# Program_Counter_Electronic_Scheme_2021-1.net
KiCad netlist of a schematic drawn in Altium Designer
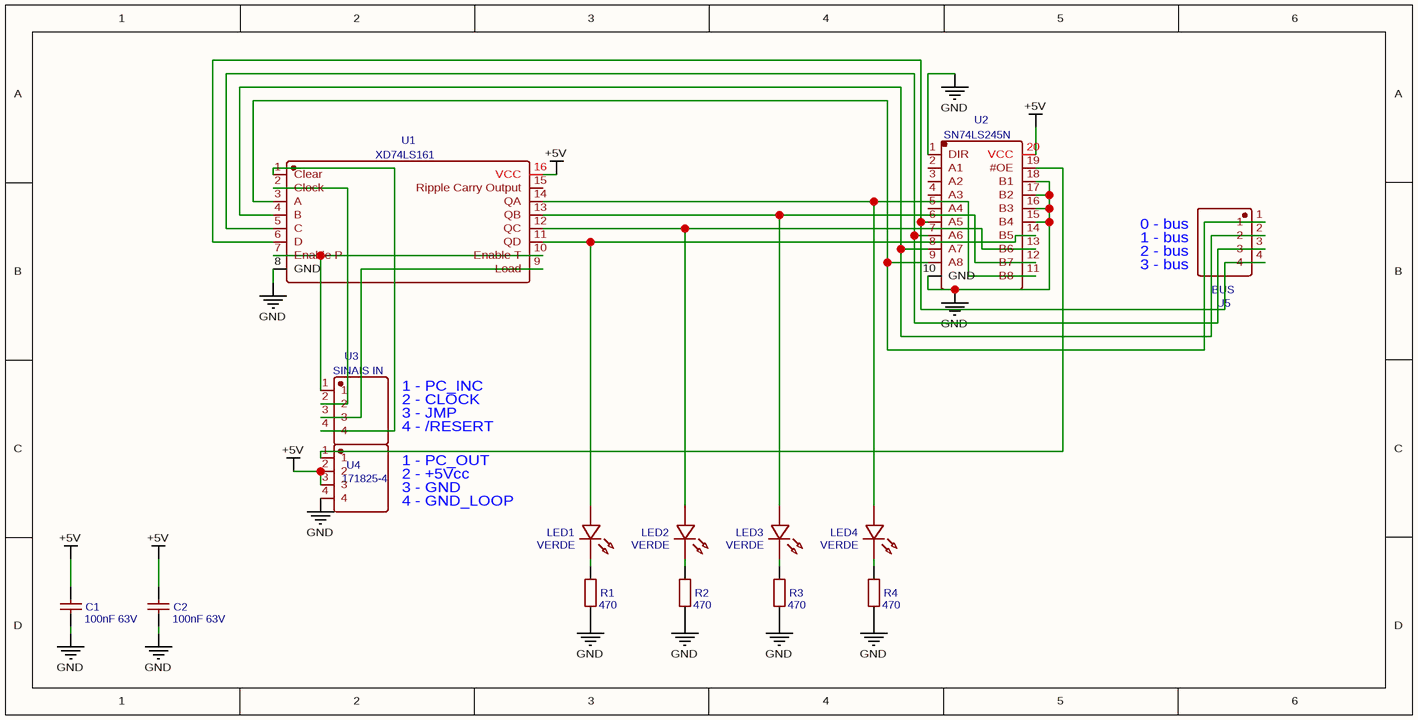
[diagram p0: Program Counter Electronic Scheme_2021-10-28.schdoc]

(export (version "E")
  (design (tool "Eeschema 10.0.6"))
  (components
    (comp (ref "C1")
      (value "100nF 63V")
      (fields
        (field (name "BOM_SUPPLIER PART") "C444741")
        (field (name "BOM_MANUFACTURER PART") "SR305C105KAR")
        (field (name "CONTRIBUTOR") "LCSC")
      )
      (libsource (lib "altium-import") (part "root_3_100nF 63V_"))
    )
    (comp (ref "C2")
      (value "100nF 63V")
      (fields
        (field (name "BOM_SUPPLIER PART") "C444741")
        (field (name "BOM_MANUFACTURER PART") "SR305C105KAR")
        (field (name "CONTRIBUTOR") "LCSC")
      )
      (libsource (lib "altium-import") (part "root_3_100nF 63V_"))
    )
    (comp (ref "LED1")
      (value "VERDE")
      (fields
        (field (name "BOM_SUPPLIER PART") "C605465")
        (field (name "BOM_MANUFACTURER PART") "264-7GD")
        (field (name "CONTRIBUTOR") "LCSC")
      )
      (libsource (lib "altium-import") (part "root_1_VERDE_"))
    )
    (comp (ref "LED2")
      (value "VERDE")
      (fields
        (field (name "BOM_SUPPLIER PART") "C605465")
        (field (name "BOM_MANUFACTURER PART") "264-7GD")
        (field (name "CONTRIBUTOR") "LCSC")
      )
      (libsource (lib "altium-import") (part "root_1_VERDE_"))
    )
    (comp (ref "LED3")
      (value "VERDE")
      (fields
        (field (name "BOM_SUPPLIER PART") "C605465")
        (field (name "BOM_MANUFACTURER PART") "264-7GD")
        (field (name "CONTRIBUTOR") "LCSC")
      )
      (libsource (lib "altium-import") (part "root_1_VERDE_"))
    )
    (comp (ref "LED4")
      (value "VERDE")
      (fields
        (field (name "BOM_SUPPLIER PART") "C605465")
        (field (name "BOM_MANUFACTURER PART") "264-7GD")
        (field (name "CONTRIBUTOR") "LCSC")
      )
      (libsource (lib "altium-import") (part "root_1_VERDE_"))
    )
    (comp (ref "R1")
      (value "470")
      (fields
        (field (name "BOM_MANUFACTURER PART") "CFR02SJ0823A10")
        (field (name "BOM_SUPPLIER PART") "C69876")
      )
      (libsource (lib "altium-import") (part "root_3_470_"))
    )
    (comp (ref "R2")
      (value "470")
      (fields
        (field (name "BOM_MANUFACTURER PART") "CFR02SJ0823A10")
        (field (name "BOM_SUPPLIER PART") "C69876")
      )
      (libsource (lib "altium-import") (part "root_3_470_"))
    )
    (comp (ref "R3")
      (value "470")
      (fields
        (field (name "BOM_MANUFACTURER PART") "CFR02SJ0823A10")
        (field (name "BOM_SUPPLIER PART") "C69876")
      )
      (libsource (lib "altium-import") (part "root_3_470_"))
    )
    (comp (ref "R4")
      (value "470")
      (fields
        (field (name "BOM_MANUFACTURER PART") "CFR02SJ0823A10")
        (field (name "BOM_SUPPLIER PART") "C69876")
      )
      (libsource (lib "altium-import") (part "root_3_470_"))
    )
    (comp (ref "U1")
      (value "XD74LS161")
      (fields (field (name "BOM_SUPPLIER PART") "C609766") (field (name "CONTRIBUTOR") "LCSC"))
      (libsource (lib "altium-import") (part "root_0_XD74LS161_"))
    )
    (comp (ref "U2")
      (value "SN74LS245N")
      (fields (field (name "BOM_SUPPLIER PART") "C352966") (field (name "CONTRIBUTOR") "LCSC"))
      (libsource (lib "altium-import") (part "root_0_SN74LS245N_"))
    )
    (comp (ref "U3")
      (value "SINAIS IN")
      (fields
        (field (name "BOM_SUPPLIER PART") "C210162")
        (field (name "BOM_MANUFACTURER PART") "171825-4")
        (field (name "CONTRIBUTOR") "LCSC")
      )
      (libsource (lib "altium-import") (part "root_0_SINAIS IN_"))
    )
    (comp (ref "U4")
      (value "171825-4")
      (fields (field (name "BOM_SUPPLIER PART") "C210162") (field (name "CONTRIBUTOR") "LCSC"))
      (libsource (lib "altium-import") (part "root_0_171825-4_"))
    )
    (comp (ref "U5")
      (value "BUS")
      (fields
        (field (name "BOM_SUPPLIER PART") "C210162")
        (field (name "BOM_MANUFACTURER PART") "171825-4")
        (field (name "CONTRIBUTOR") "LCSC")
      )
      (libsource (lib "altium-import") (part "root_2_BUS_"))
    )
  )
  (nets
    (net (code "1") (name "+5V") (class "Default")
      (node (ref "C1") (pin "1") (pinfunction "1_1") (pintype "passive"))
      (node (ref "C2") (pin "1") (pinfunction "1_1") (pintype "passive"))
      (node (ref "U1") (pin "16") (pinfunction "VCC_16") (pintype "passive"))
      (node (ref "U2") (pin "20") (pinfunction "VCC_20") (pintype "passive"))
      (node (ref "U4") (pin "2") (pinfunction "2_2") (pintype "passive"))
      (node (ref "U4") (pin "3") (pinfunction "3_3") (pintype "passive"))
    )
    (net (code "2") (name "GND") (class "Default")
      (node (ref "C1") (pin "2") (pinfunction "2_2") (pintype "passive"))
      (node (ref "C2") (pin "2") (pinfunction "2_2") (pintype "passive"))
      (node (ref "R1") (pin "2") (pinfunction "2_2") (pintype "passive"))
      (node (ref "R2") (pin "2") (pinfunction "2_2") (pintype "passive"))
      (node (ref "R3") (pin "2") (pinfunction "2_2") (pintype "passive"))
      (node (ref "R4") (pin "2") (pinfunction "2_2") (pintype "passive"))
      (node (ref "U1") (pin "8") (pinfunction "GND_8") (pintype "passive"))
      (node (ref "U2") (pin "1") (pinfunction "DIR_1") (pintype "passive"))
      (node (ref "U2") (pin "10") (pinfunction "GND_10") (pintype "passive"))
      (node (ref "U2") (pin "15") (pinfunction "B4_15") (pintype "passive"))
      (node (ref "U2") (pin "16") (pinfunction "B3_16") (pintype "passive"))
      (node (ref "U2") (pin "17") (pinfunction "B2_17") (pintype "passive"))
      (node (ref "U2") (pin "18") (pinfunction "B1_18") (pintype "passive"))
      (node (ref "U4") (pin "4") (pinfunction "4_4") (pintype "passive"))
    )
    (net (code "3") (name "Net-(LED1-+)") (class "Default")
      (node (ref "LED1") (pin "2") (pinfunction "+_2") (pintype "passive"))
      (node (ref "U1") (pin "11") (pinfunction "QD_11") (pintype "passive"))
      (node (ref "U2") (pin "14") (pinfunction "B5_14") (pintype "passive"))
    )
    (net (code "4") (name "Net-(LED1--)") (class "Default")
      (node (ref "LED1") (pin "1") (pinfunction "-_1") (pintype "passive"))
      (node (ref "R1") (pin "1") (pinfunction "1_1") (pintype "passive"))
    )
    (net (code "5") (name "Net-(LED2-+)") (class "Default")
      (node (ref "LED2") (pin "2") (pinfunction "+_2") (pintype "passive"))
      (node (ref "U1") (pin "12") (pinfunction "QC_12") (pintype "passive"))
      (node (ref "U2") (pin "13") (pinfunction "B6_13") (pintype "passive"))
    )
    (net (code "6") (name "Net-(LED2--)") (class "Default")
      (node (ref "LED2") (pin "1") (pinfunction "-_1") (pintype "passive"))
      (node (ref "R2") (pin "1") (pinfunction "1_1") (pintype "passive"))
    )
    (net (code "7") (name "Net-(LED3-+)") (class "Default")
      (node (ref "LED3") (pin "2") (pinfunction "+_2") (pintype "passive"))
      (node (ref "U1") (pin "13") (pinfunction "QB_13") (pintype "passive"))
      (node (ref "U2") (pin "12") (pinfunction "B7_12") (pintype "passive"))
    )
    (net (code "8") (name "Net-(LED3--)") (class "Default")
      (node (ref "LED3") (pin "1") (pinfunction "-_1") (pintype "passive"))
      (node (ref "R3") (pin "1") (pinfunction "1_1") (pintype "passive"))
    )
    (net (code "9") (name "Net-(LED4-+)") (class "Default")
      (node (ref "LED4") (pin "2") (pinfunction "+_2") (pintype "passive"))
      (node (ref "U1") (pin "14") (pinfunction "QA_14") (pintype "passive"))
      (node (ref "U2") (pin "11") (pinfunction "B8_11") (pintype "passive"))
    )
    (net (code "10") (name "Net-(LED4--)") (class "Default")
      (node (ref "LED4") (pin "1") (pinfunction "-_1") (pintype "passive"))
      (node (ref "R4") (pin "1") (pinfunction "1_1") (pintype "passive"))
    )
    (net (code "11") (name "Net-(U1-A)") (class "Default")
      (node (ref "U1") (pin "3") (pinfunction "A_3") (pintype "passive"))
      (node (ref "U2") (pin "9") (pinfunction "A8_9") (pintype "passive"))
      (node (ref "U5") (pin "1") (pinfunction "1_1") (pintype "passive"))
    )
    (net (code "12") (name "Net-(U1-B)") (class "Default")
      (node (ref "U1") (pin "4") (pinfunction "B_4") (pintype "passive"))
      (node (ref "U2") (pin "8") (pinfunction "A7_8") (pintype "passive"))
      (node (ref "U5") (pin "2") (pinfunction "2_2") (pintype "passive"))
    )
    (net (code "13") (name "Net-(U1-C)") (class "Default")
      (node (ref "U1") (pin "5") (pinfunction "C_5") (pintype "passive"))
      (node (ref "U2") (pin "7") (pinfunction "A6_7") (pintype "passive"))
      (node (ref "U5") (pin "3") (pinfunction "3_3") (pintype "passive"))
    )
    (net (code "14") (name "Net-(U1-Clear)") (class "Default")
      (node (ref "U1") (pin "1") (pinfunction "Clear_1") (pintype "passive"))
      (node (ref "U3") (pin "4") (pinfunction "4_4") (pintype "passive"))
    )
    (net (code "15") (name "Net-(U1-Clock)") (class "Default")
      (node (ref "U1") (pin "2") (pinfunction "Clock_2") (pintype "passive"))
      (node (ref "U3") (pin "2") (pinfunction "2_2") (pintype "passive"))
    )
    (net (code "16") (name "Net-(U1-D)") (class "Default")
      (node (ref "U1") (pin "6") (pinfunction "D_6") (pintype "passive"))
      (node (ref "U2") (pin "6") (pinfunction "A5_6") (pintype "passive"))
      (node (ref "U5") (pin "4") (pinfunction "4_4") (pintype "passive"))
    )
    (net (code "17") (name "Net-(U1-Enable_P)") (class "Default")
      (node (ref "U1") (pin "10") (pinfunction "Enable_T_10") (pintype "passive"))
      (node (ref "U1") (pin "7") (pinfunction "Enable_P_7") (pintype "passive"))
      (node (ref "U3") (pin "1") (pinfunction "1_1") (pintype "passive"))
    )
    (net (code "18") (name "Net-(U1-Load)") (class "Default")
      (node (ref "U1") (pin "9") (pinfunction "Load_9") (pintype "passive"))
      (node (ref "U3") (pin "3") (pinfunction "3_3") (pintype "passive"))
    )
    (net (code "19") (name "Net-(U2-#OE)") (class "Default")
      (node (ref "U2") (pin "19") (pinfunction "#OE_19") (pintype "passive"))
      (node (ref "U4") (pin "1") (pinfunction "1_1") (pintype "passive"))
    )
    (net (code "20") (name "unconnected-(U1-Ripple_Carry_Output-Pad15)") (class "Default")
      (node (ref "U1") (pin "15") (pinfunction "Ripple_Carry_Output_15") (pintype "passive"))
    )
    (net (code "21") (name "unconnected-(U2-A1-Pad2)") (class "Default")
      (node (ref "U2") (pin "2") (pinfunction "A1_2") (pintype "passive"))
    )
    (net (code "22") (name "unconnected-(U2-A2-Pad3)") (class "Default")
      (node (ref "U2") (pin "3") (pinfunction "A2_3") (pintype "passive"))
    )
    (net (code "23") (name "unconnected-(U2-A3-Pad4)") (class "Default")
      (node (ref "U2") (pin "4") (pinfunction "A3_4") (pintype "passive"))
    )
    (net (code "24") (name "unconnected-(U2-A4-Pad5)") (class "Default")
      (node (ref "U2") (pin "5") (pinfunction "A4_5") (pintype "passive"))
    )
  )
)
